# Est_gio_1_-_Diferencial.net
KiCad netlist of a schematic drawn in Altium Designer
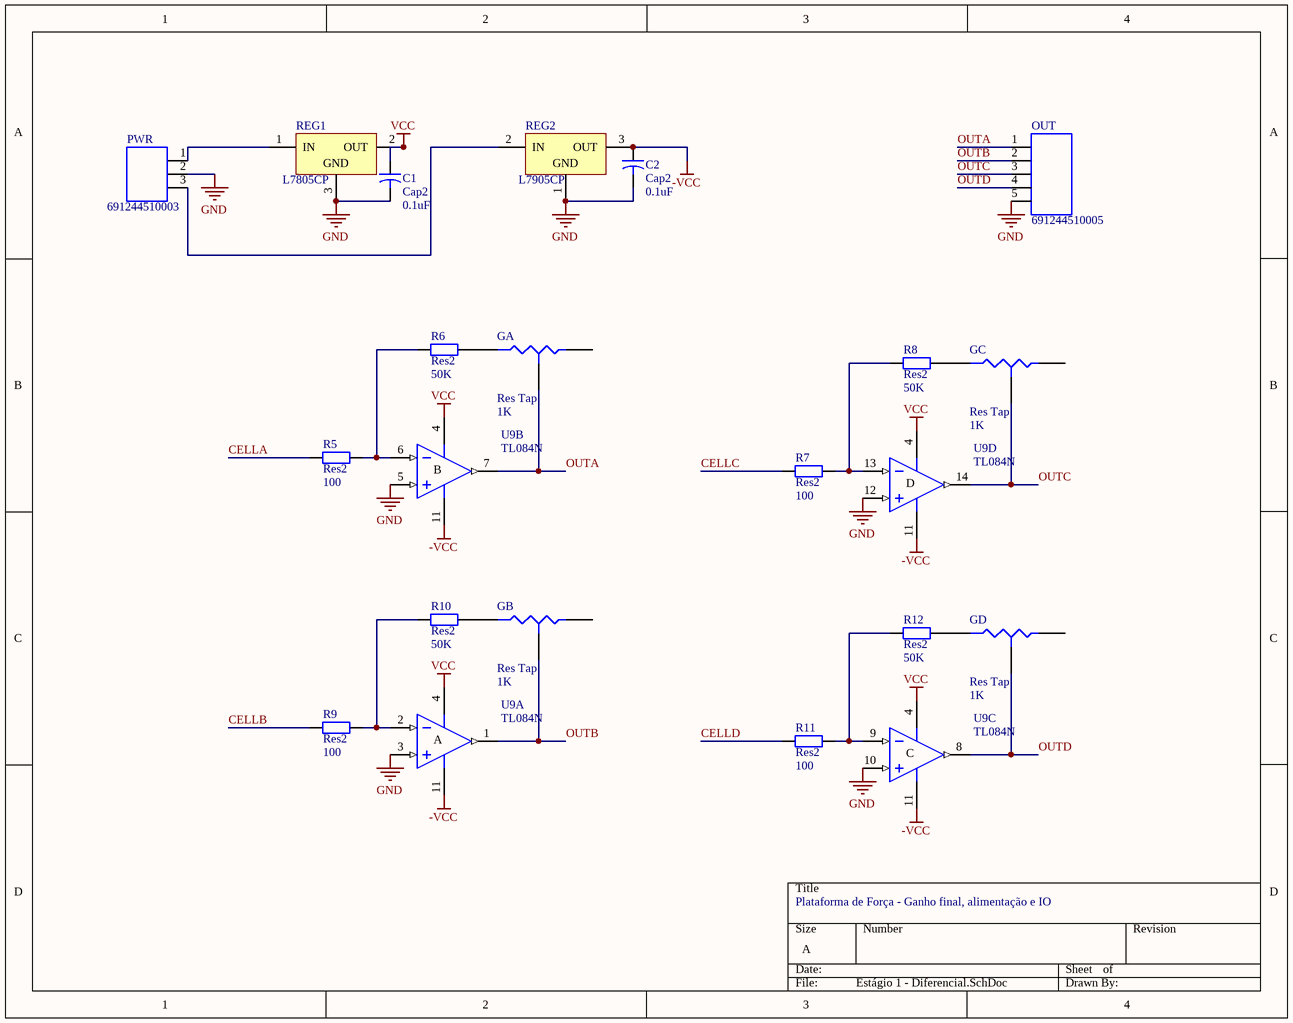
[diagram p0: Estágio 1 - Diferencial.SchDoc]

(export (version "E")
  (design (tool "Eeschema 10.0.6"))
  (components
    (comp (ref "C1")
      (value "Cap2")
      (footprint "CAPR5-4X5")
      (description "Capacitor")
      (fields (field (name "ALTIUM_VALUE") "0.1uF") (field (name "PUBLISHER") "Altium Limited"))
      (libsource (lib "Miscellaneous Devices") (part "Cap2"))
    )
    (comp (ref "C2")
      (value "Cap2")
      (footprint "CAPR5-4X5")
      (description "Capacitor")
      (fields (field (name "ALTIUM_VALUE") "0.1uF") (field (name "PUBLISHER") "Altium Limited"))
      (libsource (lib "Miscellaneous Devices") (part "Cap2"))
    )
    (comp (ref "GA")
      (value "Res Tap")
      (footprint "3296W")
      (description "Tapped Resistor")
      (fields (field (name "ALTIUM_VALUE") "1K") (field (name "PUBLISHER") "Altium Limited"))
      (libsource (lib "Miscellaneous Devices") (part "Res Tap"))
    )
    (comp (ref "GB")
      (value "Res Tap")
      (footprint "3296W")
      (description "Tapped Resistor")
      (fields (field (name "ALTIUM_VALUE") "1K") (field (name "PUBLISHER") "Altium Limited"))
      (libsource (lib "Miscellaneous Devices") (part "Res Tap"))
    )
    (comp (ref "GC")
      (value "Res Tap")
      (footprint "3296W")
      (description "Tapped Resistor")
      (fields (field (name "ALTIUM_VALUE") "1K") (field (name "PUBLISHER") "Altium Limited"))
      (libsource (lib "Miscellaneous Devices") (part "Res Tap"))
    )
    (comp (ref "GD")
      (value "Res Tap")
      (footprint "3296W")
      (description "Tapped Resistor")
      (fields (field (name "ALTIUM_VALUE") "1K") (field (name "PUBLISHER") "Altium Limited"))
      (libsource (lib "Miscellaneous Devices") (part "Res Tap"))
    )
    (comp (ref "OUT")
      (value "691244510005")
      (footprint "691244510005")
      (description "WR-TBL Horizontal Cable Entry With Rising Cage Clamp,Serie 2445 - 5.08 mm")
      (fields (field (name "MANUFACTURER") "Wurth Elektronik") (field (name "CREATED BY") "Baojun Chen"))
      (libsource (lib "WE_WR-TBL_Rising Cage System_5.08 mm_rev15b") (part "691244510005"))
    )
    (comp (ref "PWR")
      (value "691244510003")
      (footprint "691244510003")
      (description "WR-TBL Horizontal Cable Entry With Rising Cage Clamp,Serie 2445 - 5.08 mm")
      (fields (field (name "MANUFACTURER") "Wurth Elektronik") (field (name "CREATED BY") "Baojun Chen"))
      (libsource (lib "WE_WR-TBL_Rising Cage System_5.08 mm_rev15b") (part "691244510003"))
    )
    (comp (ref "R5")
      (value "Res2")
      (footprint "AXIAL-0.4")
      (description "Resistor")
      (fields (field (name "ALTIUM_VALUE") "100") (field (name "PUBLISHER") "Altium Limited"))
      (libsource (lib "Miscellaneous Devices") (part "Res2"))
    )
    (comp (ref "R6")
      (value "Res2")
      (footprint "AXIAL-0.4")
      (description "Resistor")
      (fields (field (name "ALTIUM_VALUE") "50K") (field (name "PUBLISHER") "Altium Limited"))
      (libsource (lib "Miscellaneous Devices") (part "Res2"))
    )
    (comp (ref "R7")
      (value "Res2")
      (footprint "AXIAL-0.4")
      (description "Resistor")
      (fields (field (name "ALTIUM_VALUE") "100") (field (name "PUBLISHER") "Altium Limited"))
      (libsource (lib "Miscellaneous Devices") (part "Res2"))
    )
    (comp (ref "R8")
      (value "Res2")
      (footprint "AXIAL-0.4")
      (description "Resistor")
      (fields (field (name "ALTIUM_VALUE") "50K") (field (name "PUBLISHER") "Altium Limited"))
      (libsource (lib "Miscellaneous Devices") (part "Res2"))
    )
    (comp (ref "R9")
      (value "Res2")
      (footprint "AXIAL-0.4")
      (description "Resistor")
      (fields (field (name "ALTIUM_VALUE") "100") (field (name "PUBLISHER") "Altium Limited"))
      (libsource (lib "Miscellaneous Devices") (part "Res2"))
    )
    (comp (ref "R10")
      (value "Res2")
      (footprint "AXIAL-0.4")
      (description "Resistor")
      (fields (field (name "ALTIUM_VALUE") "50K") (field (name "PUBLISHER") "Altium Limited"))
      (libsource (lib "Miscellaneous Devices") (part "Res2"))
    )
    (comp (ref "R11")
      (value "Res2")
      (footprint "AXIAL-0.4")
      (description "Resistor")
      (fields (field (name "ALTIUM_VALUE") "100") (field (name "PUBLISHER") "Altium Limited"))
      (libsource (lib "Miscellaneous Devices") (part "Res2"))
    )
    (comp (ref "R12")
      (value "Res2")
      (footprint "AXIAL-0.4")
      (description "Resistor")
      (fields (field (name "ALTIUM_VALUE") "50K") (field (name "PUBLISHER") "Altium Limited"))
      (libsource (lib "Miscellaneous Devices") (part "Res2"))
    )
    (comp (ref "REG1")
      (value "L7805CP")
      (footprint "ISOWATT220AB")
      (description "Positive Voltage Regulator")
      (fields (field (name "PUBLISHER") "Altium Limited"))
      (libsource (lib "ST Power Mgt Voltage Regulator") (part "L7805CP"))
    )
    (comp (ref "REG2")
      (value "L7905CP")
      (footprint "ISOWATT220AB")
      (description "Negative Voltage Regulator")
      (fields (field (name "PUBLISHER") "Altium Limited"))
      (libsource (lib "ST Power Mgt Voltage Regulator") (part "L7905CP"))
    )
    (comp (ref "U9")
      (value "TL084N")
      (footprint "N014")
      (description "JFET-Input Operational Amplifier")
      (fields (field (name "PUBLISHER") "Altium Limited"))
      (libsource (lib "TI Operational Amplifier") (part "TL084N"))
    )
  )
  (nets
    (net (code "1") (name "-VCC") (class "Default")
      (node (ref "C2") (pin "1") (pinfunction "1_1") (pintype "passive"))
      (node (ref "REG2") (pin "3") (pinfunction "OUT_3") (pintype "power_in"))
      (node (ref "U9") (pin "11") (pinfunction "V-_11") (pintype "power_in"))
    )
    (net (code "2") (name "/CELLA") (class "Default")
      (node (ref "R5") (pin "1") (pinfunction "1_1") (pintype "passive"))
    )
    (net (code "3") (name "/CELLB") (class "Default")
      (node (ref "R9") (pin "1") (pinfunction "1_1") (pintype "passive"))
    )
    (net (code "4") (name "/CELLC") (class "Default")
      (node (ref "R7") (pin "1") (pinfunction "1_1") (pintype "passive"))
    )
    (net (code "5") (name "/CELLD") (class "Default")
      (node (ref "R11") (pin "1") (pinfunction "1_1") (pintype "passive"))
    )
    (net (code "6") (name "/OUTA") (class "Default")
      (node (ref "GA") (pin "3") (pinfunction "TAP_3") (pintype "passive"))
      (node (ref "OUT") (pin "1") (pinfunction "1_1") (pintype "passive"))
      (node (ref "U9") (pin "7") (pinfunction "OUT_7") (pintype "output"))
    )
    (net (code "7") (name "/OUTB") (class "Default")
      (node (ref "GB") (pin "3") (pinfunction "TAP_3") (pintype "passive"))
      (node (ref "OUT") (pin "2") (pinfunction "2_2") (pintype "passive"))
      (node (ref "U9") (pin "1") (pinfunction "OUT_1") (pintype "output"))
    )
    (net (code "8") (name "/OUTC") (class "Default")
      (node (ref "GC") (pin "3") (pinfunction "TAP_3") (pintype "passive"))
      (node (ref "OUT") (pin "3") (pinfunction "3_3") (pintype "passive"))
      (node (ref "U9") (pin "14") (pinfunction "OUT_14") (pintype "output"))
    )
    (net (code "9") (name "/OUTD") (class "Default")
      (node (ref "GD") (pin "3") (pinfunction "TAP_3") (pintype "passive"))
      (node (ref "OUT") (pin "4") (pinfunction "4_4") (pintype "passive"))
      (node (ref "U9") (pin "8") (pinfunction "OUT_8") (pintype "output"))
    )
    (net (code "10") (name "GND") (class "Default")
      (node (ref "C1") (pin "2") (pinfunction "2_2") (pintype "passive"))
      (node (ref "C2") (pin "2") (pinfunction "2_2") (pintype "passive"))
      (node (ref "OUT") (pin "5") (pinfunction "5_5") (pintype "passive"))
      (node (ref "PWR") (pin "2") (pinfunction "2_2") (pintype "passive"))
      (node (ref "REG1") (pin "3") (pinfunction "GND_3") (pintype "power_in"))
      (node (ref "REG2") (pin "1") (pinfunction "GND_1") (pintype "power_in"))
      (node (ref "U9") (pin "10") (pinfunction "IN+_10") (pintype "input"))
      (node (ref "U9") (pin "12") (pinfunction "IN+_12") (pintype "input"))
      (node (ref "U9") (pin "3") (pinfunction "IN+_3") (pintype "input"))
      (node (ref "U9") (pin "5") (pinfunction "IN+_5") (pintype "input"))
    )
    (net (code "11") (name "Net-(GA-B)") (class "Default")
      (node (ref "GA") (pin "2") (pinfunction "B_2") (pintype "passive"))
      (node (ref "R6") (pin "2") (pinfunction "2_2") (pintype "passive"))
    )
    (net (code "12") (name "Net-(GB-B)") (class "Default")
      (node (ref "GB") (pin "2") (pinfunction "B_2") (pintype "passive"))
      (node (ref "R10") (pin "2") (pinfunction "2_2") (pintype "passive"))
    )
    (net (code "13") (name "Net-(GC-B)") (class "Default")
      (node (ref "GC") (pin "2") (pinfunction "B_2") (pintype "passive"))
      (node (ref "R8") (pin "2") (pinfunction "2_2") (pintype "passive"))
    )
    (net (code "14") (name "Net-(GD-B)") (class "Default")
      (node (ref "GD") (pin "2") (pinfunction "B_2") (pintype "passive"))
      (node (ref "R12") (pin "2") (pinfunction "2_2") (pintype "passive"))
    )
    (net (code "15") (name "Net-(REG1-IN)") (class "Default")
      (node (ref "PWR") (pin "1") (pinfunction "1_1") (pintype "passive"))
      (node (ref "REG1") (pin "1") (pinfunction "IN_1") (pintype "power_in"))
    )
    (net (code "16") (name "Net-(REG2-IN)") (class "Default")
      (node (ref "PWR") (pin "3") (pinfunction "3_3") (pintype "passive"))
      (node (ref "REG2") (pin "2") (pinfunction "IN_2") (pintype "power_in"))
    )
    (net (code "17") (name "Net-(U9A-IN-)") (class "Default")
      (node (ref "R10") (pin "1") (pinfunction "1_1") (pintype "passive"))
      (node (ref "R9") (pin "2") (pinfunction "2_2") (pintype "passive"))
      (node (ref "U9") (pin "2") (pinfunction "IN-_2") (pintype "input"))
    )
    (net (code "18") (name "Net-(U9B-IN-)") (class "Default")
      (node (ref "R5") (pin "2") (pinfunction "2_2") (pintype "passive"))
      (node (ref "R6") (pin "1") (pinfunction "1_1") (pintype "passive"))
      (node (ref "U9") (pin "6") (pinfunction "IN-_6") (pintype "input"))
    )
    (net (code "19") (name "Net-(U9C-IN-)") (class "Default")
      (node (ref "R11") (pin "2") (pinfunction "2_2") (pintype "passive"))
      (node (ref "R12") (pin "1") (pinfunction "1_1") (pintype "passive"))
      (node (ref "U9") (pin "9") (pinfunction "IN-_9") (pintype "input"))
    )
    (net (code "20") (name "Net-(U9D-IN-)") (class "Default")
      (node (ref "R7") (pin "2") (pinfunction "2_2") (pintype "passive"))
      (node (ref "R8") (pin "1") (pinfunction "1_1") (pintype "passive"))
      (node (ref "U9") (pin "13") (pinfunction "IN-_13") (pintype "input"))
    )
    (net (code "21") (name "VCC") (class "Default")
      (node (ref "C1") (pin "1") (pinfunction "1_1") (pintype "passive"))
      (node (ref "REG1") (pin "2") (pinfunction "OUT_2") (pintype "power_in"))
      (node (ref "U9") (pin "4") (pinfunction "V+_4") (pintype "power_in"))
    )
    (net (code "22") (name "unconnected-(GA-A-Pad1)") (class "Default")
      (node (ref "GA") (pin "1") (pinfunction "A_1") (pintype "passive"))
    )
    (net (code "23") (name "unconnected-(GB-A-Pad1)") (class "Default")
      (node (ref "GB") (pin "1") (pinfunction "A_1") (pintype "passive"))
    )
    (net (code "24") (name "unconnected-(GC-A-Pad1)") (class "Default")
      (node (ref "GC") (pin "1") (pinfunction "A_1") (pintype "passive"))
    )
    (net (code "25") (name "unconnected-(GD-A-Pad1)") (class "Default")
      (node (ref "GD") (pin "1") (pinfunction "A_1") (pintype "passive"))
    )
  )
)
